# Connector.net
KiCad netlist of a schematic drawn in Altium Designer
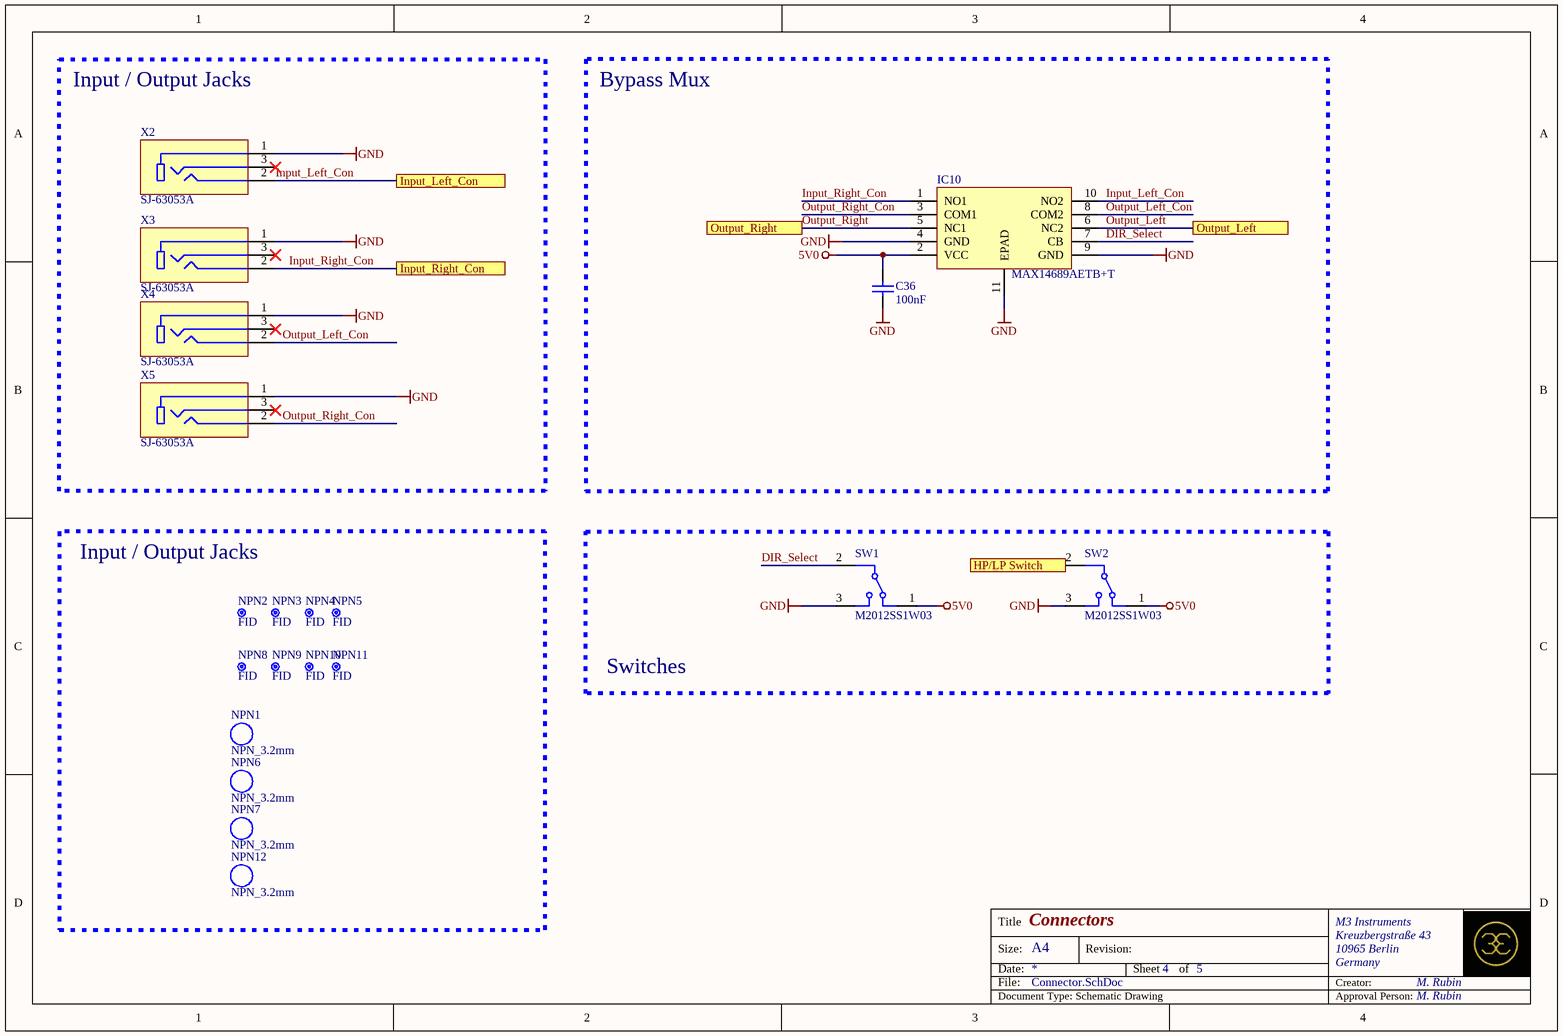
[diagram p0: Connector.SchDoc]

(export (version "E")
  (design (tool "Eeschema 10.0.6"))
  (components
    (comp (ref "C36")
      (value "100nF")
      (footprint "CAPC1608X95N")
      (description "Multilayer Ceramic Capacitors MLCC - SMD/SMT, 100nF")
      (fields
        (field (name "MANUFACTURER") "YAGEO")
        (field (name "MANUFACTURER PART NUMBER") "CC0603KRX7R9BB104")
      )
      (libsource (lib "Caps") (part "CAP_100nF_0603"))
    )
    (comp (ref "IC10")
      (value "MAX14689AETB+T")
      (footprint "QFN40P200X250X80_HS-11N")
      (description "Analogue Switch ICs Ultra-Small, Low-RON, Beyond-the-Rails™, DPDT Analog Switches")
      (fields (field (name "MANUFACTURER") "Maxim Integrated"))
      (libsource (lib "ICs") (part "IC_MAX14689AETB+T"))
    )
    (comp (ref "NPN1")
      (value "NPN_3.2mm")
      (footprint "HOLE_NPH_3.2_M3")
      (libsource (lib "MISC") (part "NPH_3.2mm_M3"))
    )
    (comp (ref "NPN2")
      (value "FID")
      (footprint "Fiducial_1mm")
      (libsource (lib "MISC") (part "Fiducial_1mm"))
    )
    (comp (ref "NPN3")
      (value "FID")
      (footprint "Fiducial_1mm")
      (libsource (lib "MISC") (part "Fiducial_1mm"))
    )
    (comp (ref "NPN4")
      (value "FID")
      (footprint "Fiducial_1mm")
      (libsource (lib "MISC") (part "Fiducial_1mm"))
    )
    (comp (ref "NPN5")
      (value "FID")
      (footprint "Fiducial_1mm")
      (libsource (lib "MISC") (part "Fiducial_1mm"))
    )
    (comp (ref "NPN6")
      (value "NPN_3.2mm")
      (footprint "HOLE_NPH_3.2_M3")
      (libsource (lib "MISC") (part "NPH_3.2mm_M3"))
    )
    (comp (ref "NPN7")
      (value "NPN_3.2mm")
      (footprint "HOLE_NPH_3.2_M3")
      (libsource (lib "MISC") (part "NPH_3.2mm_M3"))
    )
    (comp (ref "NPN8")
      (value "FID")
      (footprint "Fiducial_1mm")
      (libsource (lib "MISC") (part "Fiducial_1mm"))
    )
    (comp (ref "NPN9")
      (value "FID")
      (footprint "Fiducial_1mm")
      (libsource (lib "MISC") (part "Fiducial_1mm"))
    )
    (comp (ref "NPN10")
      (value "FID")
      (footprint "Fiducial_1mm")
      (libsource (lib "MISC") (part "Fiducial_1mm"))
    )
    (comp (ref "NPN11")
      (value "FID")
      (footprint "Fiducial_1mm")
      (libsource (lib "MISC") (part "Fiducial_1mm"))
    )
    (comp (ref "NPN12")
      (value "NPN_3.2mm")
      (footprint "HOLE_NPH_3.2_M3")
      (libsource (lib "MISC") (part "NPH_3.2mm_M3"))
    )
    (comp (ref "SW1")
      (value "M2012SS1W03")
      (footprint "M2012SS1W03")
      (description "Kippschalter SPDT Panelmontage")
      (fields (field (name "MANUFACTURER") "NKK Switches"))
      (libsource (lib "Switches") (part "SW_M2012SS1W03"))
    )
    (comp (ref "SW2")
      (value "M2012SS1W03")
      (footprint "M2012SS1W03")
      (description "Kippschalter SPDT Panelmontage")
      (fields (field (name "MANUFACTURER") "NKK Switches"))
      (libsource (lib "Switches") (part "SW_M2012SS1W03"))
    )
    (comp (ref "X2")
      (value "SJ-63053A")
      (footprint "CUI_SJ-63053A")
      (fields (field (name "MANUFACTURER") "CUI Devices"))
      (libsource (lib "Connectors") (part "Phone_Jack_1/4_SJ-63053A"))
    )
    (comp (ref "X3")
      (value "SJ-63053A")
      (footprint "CUI_SJ-63053A")
      (fields (field (name "MANUFACTURER") "CUI Devices"))
      (libsource (lib "Connectors") (part "Phone_Jack_1/4_SJ-63053A"))
    )
    (comp (ref "X4")
      (value "SJ-63053A")
      (footprint "CUI_SJ-63053A")
      (fields (field (name "MANUFACTURER") "CUI Devices"))
      (libsource (lib "Connectors") (part "Phone_Jack_1/4_SJ-63053A"))
    )
    (comp (ref "X5")
      (value "SJ-63053A")
      (footprint "CUI_SJ-63053A")
      (fields (field (name "MANUFACTURER") "CUI Devices"))
      (libsource (lib "Connectors") (part "Phone_Jack_1/4_SJ-63053A"))
    )
  )
  (nets
    (net (code "1") (name "/DIR_Select") (class "Default")
      (node (ref "IC10") (pin "7") (pinfunction "CB_7") (pintype "passive"))
      (node (ref "SW1") (pin "2") (pinfunction "2_2") (pintype "passive"))
    )
    (net (code "2") (name "/HP{slash}LP Switch") (class "Default")
      (node (ref "SW2") (pin "2") (pinfunction "2_2") (pintype "passive"))
    )
    (net (code "3") (name "/Input_Left_Con") (class "Default")
      (node (ref "IC10") (pin "10") (pinfunction "NO2_10") (pintype "passive"))
      (node (ref "X2") (pin "2") (pinfunction "2_2") (pintype "passive"))
    )
    (net (code "4") (name "/Input_Right_Con") (class "Default")
      (node (ref "IC10") (pin "1") (pinfunction "NO1_1") (pintype "passive"))
      (node (ref "X3") (pin "2") (pinfunction "2_2") (pintype "passive"))
    )
    (net (code "5") (name "/Output_Left") (class "Default")
      (node (ref "IC10") (pin "6") (pinfunction "NC2_6") (pintype "passive"))
    )
    (net (code "6") (name "/Output_Left_Con") (class "Default")
      (node (ref "IC10") (pin "8") (pinfunction "COM2_8") (pintype "passive"))
      (node (ref "X4") (pin "2") (pinfunction "2_2") (pintype "passive"))
    )
    (net (code "7") (name "/Output_Right") (class "Default")
      (node (ref "IC10") (pin "5") (pinfunction "NC1_5") (pintype "passive"))
    )
    (net (code "8") (name "/Output_Right_Con") (class "Default")
      (node (ref "IC10") (pin "3") (pinfunction "COM1_3") (pintype "passive"))
      (node (ref "X5") (pin "2") (pinfunction "2_2") (pintype "passive"))
    )
    (net (code "9") (name "5V0") (class "Default")
      (node (ref "C36") (pin "1") (pinfunction "1_1") (pintype "passive"))
      (node (ref "IC10") (pin "2") (pinfunction "VCC_2") (pintype "passive"))
      (node (ref "SW1") (pin "1") (pinfunction "1_1") (pintype "passive"))
      (node (ref "SW2") (pin "1") (pinfunction "1_1") (pintype "passive"))
    )
    (net (code "10") (name "GND") (class "Default")
      (node (ref "C36") (pin "2") (pinfunction "2_2") (pintype "passive"))
      (node (ref "IC10") (pin "11") (pinfunction "EPAD_11") (pintype "passive"))
      (node (ref "IC10") (pin "4") (pinfunction "GND_4") (pintype "passive"))
      (node (ref "IC10") (pin "9") (pinfunction "GND_9") (pintype "passive"))
      (node (ref "SW1") (pin "3") (pinfunction "3_3") (pintype "passive"))
      (node (ref "SW2") (pin "3") (pinfunction "3_3") (pintype "passive"))
      (node (ref "X2") (pin "1") (pinfunction "1_1") (pintype "passive"))
      (node (ref "X3") (pin "1") (pinfunction "1_1") (pintype "passive"))
      (node (ref "X4") (pin "1") (pinfunction "1_1") (pintype "passive"))
      (node (ref "X5") (pin "1") (pinfunction "1_1") (pintype "passive"))
    )
    (net (code "11") (name "unconnected-(X2-Pad3)") (class "Default")
      (node (ref "X2") (pin "3") (pinfunction "3_3") (pintype "passive+no_connect"))
    )
    (net (code "12") (name "unconnected-(X3-Pad3)") (class "Default")
      (node (ref "X3") (pin "3") (pinfunction "3_3") (pintype "passive+no_connect"))
    )
    (net (code "13") (name "unconnected-(X4-Pad3)") (class "Default")
      (node (ref "X4") (pin "3") (pinfunction "3_3") (pintype "passive+no_connect"))
    )
    (net (code "14") (name "unconnected-(X5-Pad3)") (class "Default")
      (node (ref "X5") (pin "3") (pinfunction "3_3") (pintype "passive+no_connect"))
    )
  )
)
